# 02_MCU.net
KiCad netlist of a schematic drawn in Altium Designer
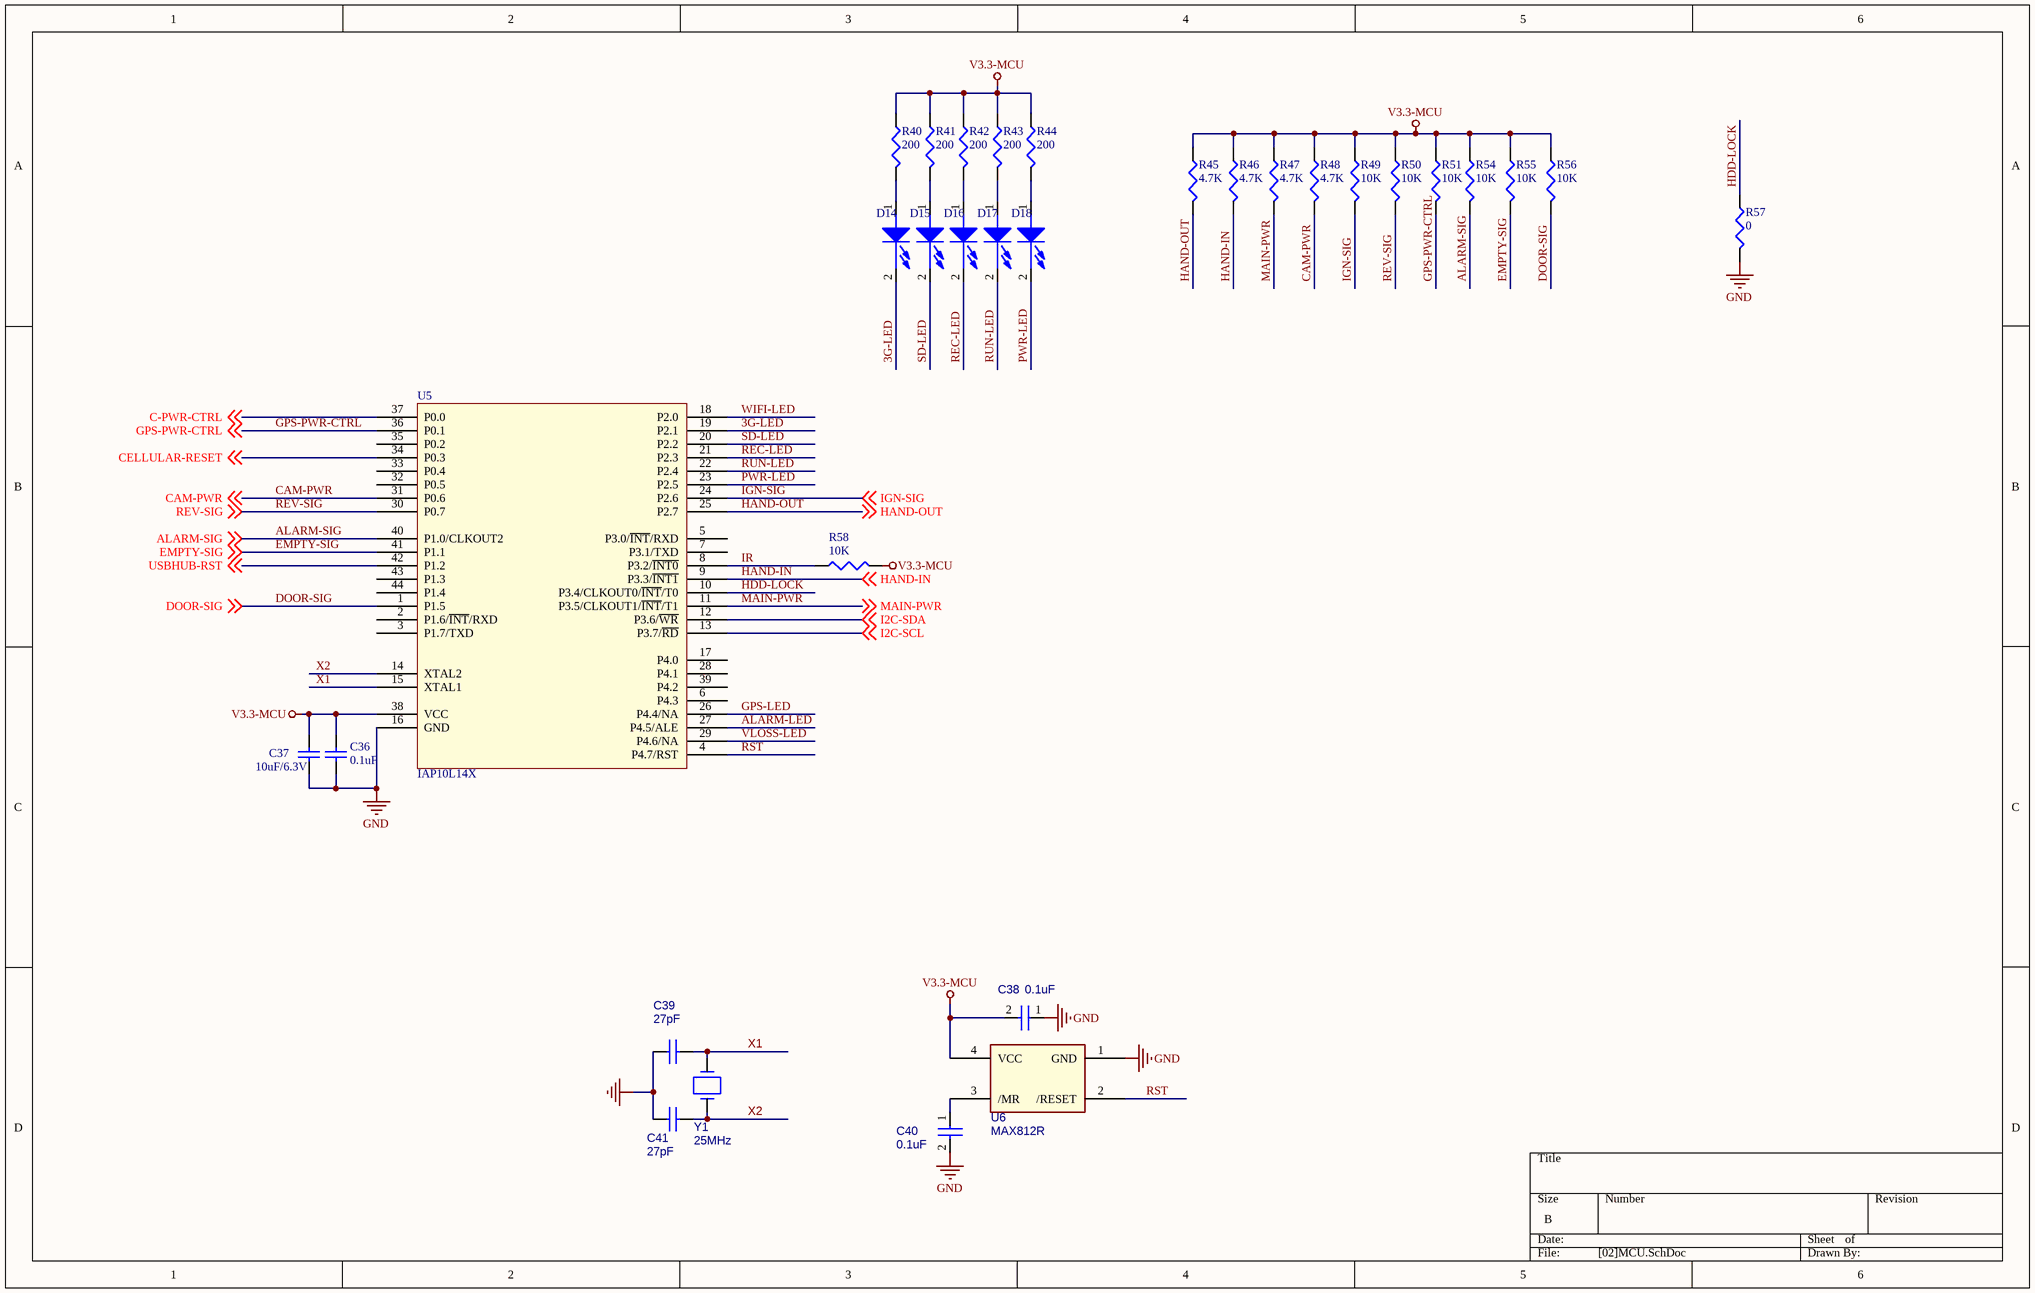
[diagram p0: [02]MCU.SchDoc]

(export (version "E")
  (design (tool "Eeschema 10.0.6"))
  (components
    (comp (ref "C36")
      (value "0.1uF")
      (footprint "0603")
      (description "Capacitor")
      (libsource (lib "Miscellaneous Devices") (part "Cap"))
    )
    (comp (ref "C37")
      (value "10uF/6.3V")
      (footprint "0805")
      (description "Capacitor")
      (libsource (lib "Miscellaneous Devices") (part "Cap"))
    )
    (comp (ref "C38") (value "0.1uF") (libsource (lib "*") (part "CAP NP_Dup2")))
    (comp (ref "C39") (value "27pF") (libsource (lib "*") (part "CAP_Dup1")))
    (comp (ref "C40") (value "0.1uF") (libsource (lib "*") (part "CAP NP_Dup2")))
    (comp (ref "C41") (value "27pF") (libsource (lib "*") (part "CAP_Dup1")))
    (comp (ref "D14") (value "LED GREEN") (footprint "LED0603") (libsource (lib "*") (part "LN01401_1")))
    (comp (ref "D15") (value "LED GREEN") (footprint "LED0603") (libsource (lib "*") (part "LN01401_1")))
    (comp (ref "D16") (value "LED GREEN") (footprint "LED0603") (libsource (lib "*") (part "LN01401_1")))
    (comp (ref "D17") (value "LED GREEN") (footprint "LED0603") (libsource (lib "*") (part "LN01401_1")))
    (comp (ref "D18") (value "LED GREEN") (footprint "LED0603") (libsource (lib "*") (part "LN01401_1")))
    (comp (ref "R40") (value "200") (footprint "0603") (libsource (lib "*") (part "CR16-1003FM")))
    (comp (ref "R41") (value "200") (footprint "0603") (libsource (lib "*") (part "CR16-1003FM")))
    (comp (ref "R42") (value "200") (footprint "0603") (libsource (lib "*") (part "CR16-1003FM")))
    (comp (ref "R43") (value "200") (footprint "0603") (libsource (lib "*") (part "CR16-1003FM")))
    (comp (ref "R44") (value "200") (footprint "0603") (libsource (lib "*") (part "CR16-1003FM")))
    (comp (ref "R45") (value "4.7K") (footprint "0603") (libsource (lib "*") (part "CR16-1003FM")))
    (comp (ref "R46") (value "4.7K") (footprint "0603") (libsource (lib "*") (part "CR16-1003FM")))
    (comp (ref "R47") (value "4.7K") (footprint "0603") (libsource (lib "*") (part "CR16-1003FM")))
    (comp (ref "R48") (value "4.7K") (footprint "0603") (libsource (lib "*") (part "CR16-1003FM")))
    (comp (ref "R49") (value "10K") (footprint "0603") (libsource (lib "*") (part "CR16-1003FM")))
    (comp (ref "R50") (value "10K") (footprint "0603") (libsource (lib "*") (part "CR16-1003FM")))
    (comp (ref "R51") (value "10K") (footprint "0603") (libsource (lib "*") (part "CR16-1003FM")))
    (comp (ref "R54") (value "10K") (footprint "0603") (libsource (lib "*") (part "CR16-1003FM")))
    (comp (ref "R55") (value "10K") (footprint "0603") (libsource (lib "*") (part "CR16-1003FM")))
    (comp (ref "R56") (value "10K") (footprint "0603") (libsource (lib "*") (part "CR16-1003FM")))
    (comp (ref "R57") (value "0") (footprint "0603") (libsource (lib "*") (part "CR16-1003FM")))
    (comp (ref "R58") (value "10K") (footprint "0603") (libsource (lib "*") (part "CR16-1003FM")))
    (comp (ref "U5") (value "IAP10L14X") (footprint "LQFP44") (libsource (lib "Schlib") (part "IAP10L14X")))
    (comp (ref "U6") (value "MAX812R") (libsource (lib "*") (part "MAX811")))
    (comp (ref "Y1") (value "25MHz") (libsource (lib "*") (part "CRYSTAL")))
  )
  (nets
    (net (code "1") (name "/3G-LED") (class "Default")
      (node (ref "D14") (pin "2") (pinfunction "CATHODE_2") (pintype "passive"))
      (node (ref "U5") (pin "19") (pinfunction "P2.1_19") (pintype "passive"))
    )
    (net (code "2") (name "/ALARM-LED") (class "Default")
      (node (ref "U5") (pin "27") (pinfunction "P4.5/ALE_27") (pintype "passive"))
    )
    (net (code "3") (name "/GPS-LED") (class "Default")
      (node (ref "U5") (pin "26") (pinfunction "P4.4/NA_26") (pintype "passive"))
    )
    (net (code "4") (name "/HDD-LOCK") (class "Default")
      (node (ref "R57") (pin "1") (pinfunction "1_1") (pintype "passive"))
      (node (ref "U5") (pin "10") (pinfunction "P3.4/CLKOUT0/~{INT}/T0_10") (pintype "passive"))
    )
    (net (code "5") (name "/IR") (class "Default")
      (node (ref "R58") (pin "1") (pinfunction "1_1") (pintype "passive"))
      (node (ref "U5") (pin "8") (pinfunction "P3.2/~{INT0}_8") (pintype "passive"))
    )
    (net (code "6") (name "/PWR-LED") (class "Default")
      (node (ref "D18") (pin "2") (pinfunction "CATHODE_2") (pintype "passive"))
      (node (ref "U5") (pin "23") (pinfunction "P2.5_23") (pintype "passive"))
    )
    (net (code "7") (name "/REC-LED") (class "Default")
      (node (ref "D16") (pin "2") (pinfunction "CATHODE_2") (pintype "passive"))
      (node (ref "U5") (pin "21") (pinfunction "P2.3_21") (pintype "passive"))
    )
    (net (code "8") (name "/RST") (class "Default")
      (node (ref "U5") (pin "4") (pinfunction "P4.7/RST_4") (pintype "passive"))
      (node (ref "U6") (pin "2") (pinfunction "/RESET_2") (pintype "passive"))
    )
    (net (code "9") (name "/RUN-LED") (class "Default")
      (node (ref "D17") (pin "2") (pinfunction "CATHODE_2") (pintype "passive"))
      (node (ref "U5") (pin "22") (pinfunction "P2.4_22") (pintype "passive"))
    )
    (net (code "10") (name "/SD-LED") (class "Default")
      (node (ref "D15") (pin "2") (pinfunction "CATHODE_2") (pintype "passive"))
      (node (ref "U5") (pin "20") (pinfunction "P2.2_20") (pintype "passive"))
    )
    (net (code "11") (name "/VLOSS-LED") (class "Default")
      (node (ref "U5") (pin "29") (pinfunction "P4.6/NA_29") (pintype "passive"))
    )
    (net (code "12") (name "/WIFI-LED") (class "Default")
      (node (ref "U5") (pin "18") (pinfunction "P2.0_18") (pintype "passive"))
    )
    (net (code "13") (name "/X1") (class "Default")
      (node (ref "C39") (pin "2") (pinfunction "2_2") (pintype "passive"))
      (node (ref "U5") (pin "15") (pinfunction "XTAL1_15") (pintype "passive"))
      (node (ref "Y1") (pin "2") (pinfunction "2_2") (pintype "passive"))
    )
    (net (code "14") (name "/X2") (class "Default")
      (node (ref "C41") (pin "2") (pinfunction "2_2") (pintype "passive"))
      (node (ref "U5") (pin "14") (pinfunction "XTAL2_14") (pintype "passive"))
      (node (ref "Y1") (pin "1") (pinfunction "1_1") (pintype "passive"))
    )
    (net (code "15") (name "ALARM-SIG") (class "Default")
      (node (ref "R54") (pin "2") (pinfunction "2_2") (pintype "passive"))
      (node (ref "U5") (pin "40") (pinfunction "P1.0/CLKOUT2_40") (pintype "passive"))
    )
    (net (code "16") (name "C-PWR-CTRL") (class "Default")
      (node (ref "U5") (pin "37") (pinfunction "P0.0_37") (pintype "passive"))
    )
    (net (code "17") (name "CAM-PWR") (class "Default")
      (node (ref "R48") (pin "2") (pinfunction "2_2") (pintype "passive"))
      (node (ref "U5") (pin "31") (pinfunction "P0.6_31") (pintype "passive"))
    )
    (net (code "18") (name "CELLULAR-RESET") (class "Default")
      (node (ref "U5") (pin "34") (pinfunction "P0.3_34") (pintype "passive"))
    )
    (net (code "19") (name "DOOR-SIG") (class "Default")
      (node (ref "R56") (pin "2") (pinfunction "2_2") (pintype "passive"))
      (node (ref "U5") (pin "1") (pinfunction "P1.5_1") (pintype "passive"))
    )
    (net (code "20") (name "EMPTY-SIG") (class "Default")
      (node (ref "R55") (pin "2") (pinfunction "2_2") (pintype "passive"))
      (node (ref "U5") (pin "41") (pinfunction "P1.1_41") (pintype "passive"))
    )
    (net (code "21") (name "GND") (class "Default")
      (node (ref "C36") (pin "1") (pinfunction "1_1") (pintype "passive"))
      (node (ref "C37") (pin "1") (pinfunction "1_1") (pintype "passive"))
      (node (ref "C38") (pin "1") (pinfunction "1_1") (pintype "passive"))
      (node (ref "C39") (pin "1") (pinfunction "1_1") (pintype "passive"))
      (node (ref "C40") (pin "2") (pinfunction "2_2") (pintype "passive"))
      (node (ref "C41") (pin "1") (pinfunction "1_1") (pintype "passive"))
      (node (ref "R57") (pin "2") (pinfunction "2_2") (pintype "passive"))
      (node (ref "U5") (pin "16") (pinfunction "GND_16") (pintype "passive"))
      (node (ref "U6") (pin "1") (pinfunction "GND_1") (pintype "passive"))
    )
    (net (code "22") (name "GPS-PWR-CTRL") (class "Default")
      (node (ref "R51") (pin "2") (pinfunction "2_2") (pintype "passive"))
      (node (ref "U5") (pin "36") (pinfunction "P0.1_36") (pintype "passive"))
    )
    (net (code "23") (name "HAND-IN") (class "Default")
      (node (ref "R46") (pin "2") (pinfunction "2_2") (pintype "passive"))
      (node (ref "U5") (pin "9") (pinfunction "P3.3/~{INT1}_9") (pintype "passive"))
    )
    (net (code "24") (name "HAND-OUT") (class "Default")
      (node (ref "R45") (pin "2") (pinfunction "2_2") (pintype "passive"))
      (node (ref "U5") (pin "25") (pinfunction "P2.7_25") (pintype "passive"))
    )
    (net (code "25") (name "I2C-SCL") (class "Default")
      (node (ref "U5") (pin "13") (pinfunction "P3.7/~{RD}_13") (pintype "passive"))
    )
    (net (code "26") (name "I2C-SDA") (class "Default")
      (node (ref "U5") (pin "12") (pinfunction "P3.6/~{WR}_12") (pintype "passive"))
    )
    (net (code "27") (name "IGN-SIG") (class "Default")
      (node (ref "R49") (pin "2") (pinfunction "2_2") (pintype "passive"))
      (node (ref "U5") (pin "24") (pinfunction "P2.6_24") (pintype "passive"))
    )
    (net (code "28") (name "MAIN-PWR") (class "Default")
      (node (ref "R47") (pin "2") (pinfunction "2_2") (pintype "passive"))
      (node (ref "U5") (pin "11") (pinfunction "P3.5/CLKOUT1/~{INT}/T1_11") (pintype "passive"))
    )
    (net (code "29") (name "Net-(D14-ANODE)") (class "Default")
      (node (ref "D14") (pin "1") (pinfunction "ANODE_1") (pintype "passive"))
      (node (ref "R40") (pin "2") (pinfunction "2_2") (pintype "passive"))
    )
    (net (code "30") (name "Net-(D15-ANODE)") (class "Default")
      (node (ref "D15") (pin "1") (pinfunction "ANODE_1") (pintype "passive"))
      (node (ref "R41") (pin "2") (pinfunction "2_2") (pintype "passive"))
    )
    (net (code "31") (name "Net-(D16-ANODE)") (class "Default")
      (node (ref "D16") (pin "1") (pinfunction "ANODE_1") (pintype "passive"))
      (node (ref "R42") (pin "2") (pinfunction "2_2") (pintype "passive"))
    )
    (net (code "32") (name "Net-(D17-ANODE)") (class "Default")
      (node (ref "D17") (pin "1") (pinfunction "ANODE_1") (pintype "passive"))
      (node (ref "R43") (pin "2") (pinfunction "2_2") (pintype "passive"))
    )
    (net (code "33") (name "Net-(D18-ANODE)") (class "Default")
      (node (ref "D18") (pin "1") (pinfunction "ANODE_1") (pintype "passive"))
      (node (ref "R44") (pin "2") (pinfunction "2_2") (pintype "passive"))
    )
    (net (code "34") (name "Net-(U6-{slash}MR)") (class "Default")
      (node (ref "C40") (pin "1") (pinfunction "1_1") (pintype "passive"))
      (node (ref "U6") (pin "3") (pinfunction "/MR_3") (pintype "passive"))
    )
    (net (code "35") (name "REV-SIG") (class "Default")
      (node (ref "R50") (pin "2") (pinfunction "2_2") (pintype "passive"))
      (node (ref "U5") (pin "30") (pinfunction "P0.7_30") (pintype "passive"))
    )
    (net (code "36") (name "USBHUB-RST") (class "Default")
      (node (ref "U5") (pin "42") (pinfunction "P1.2_42") (pintype "passive"))
    )
    (net (code "37") (name "V3.3-MCU") (class "Default")
      (node (ref "C36") (pin "2") (pinfunction "2_2") (pintype "passive"))
      (node (ref "C37") (pin "2") (pinfunction "2_2") (pintype "passive"))
      (node (ref "C38") (pin "2") (pinfunction "2_2") (pintype "passive"))
      (node (ref "R40") (pin "1") (pinfunction "1_1") (pintype "passive"))
      (node (ref "R41") (pin "1") (pinfunction "1_1") (pintype "passive"))
      (node (ref "R42") (pin "1") (pinfunction "1_1") (pintype "passive"))
      (node (ref "R43") (pin "1") (pinfunction "1_1") (pintype "passive"))
      (node (ref "R44") (pin "1") (pinfunction "1_1") (pintype "passive"))
      (node (ref "R45") (pin "1") (pinfunction "1_1") (pintype "passive"))
      (node (ref "R46") (pin "1") (pinfunction "1_1") (pintype "passive"))
      (node (ref "R47") (pin "1") (pinfunction "1_1") (pintype "passive"))
      (node (ref "R48") (pin "1") (pinfunction "1_1") (pintype "passive"))
      (node (ref "R49") (pin "1") (pinfunction "1_1") (pintype "passive"))
      (node (ref "R50") (pin "1") (pinfunction "1_1") (pintype "passive"))
      (node (ref "R51") (pin "1") (pinfunction "1_1") (pintype "passive"))
      (node (ref "R54") (pin "1") (pinfunction "1_1") (pintype "passive"))
      (node (ref "R55") (pin "1") (pinfunction "1_1") (pintype "passive"))
      (node (ref "R56") (pin "1") (pinfunction "1_1") (pintype "passive"))
      (node (ref "R58") (pin "2") (pinfunction "2_2") (pintype "passive"))
      (node (ref "U5") (pin "38") (pinfunction "VCC_38") (pintype "passive"))
      (node (ref "U6") (pin "4") (pinfunction "VCC_4") (pintype "passive"))
    )
    (net (code "38") (name "unconnected-(U5-P0.2-Pad35)") (class "Default")
      (node (ref "U5") (pin "35") (pinfunction "P0.2_35") (pintype "passive"))
    )
    (net (code "39") (name "unconnected-(U5-P0.4-Pad33)") (class "Default")
      (node (ref "U5") (pin "33") (pinfunction "P0.4_33") (pintype "passive"))
    )
    (net (code "40") (name "unconnected-(U5-P0.5-Pad32)") (class "Default")
      (node (ref "U5") (pin "32") (pinfunction "P0.5_32") (pintype "passive"))
    )
    (net (code "41") (name "unconnected-(U5-P1.3-Pad43)") (class "Default")
      (node (ref "U5") (pin "43") (pinfunction "P1.3_43") (pintype "passive"))
    )
    (net (code "42") (name "unconnected-(U5-P1.4-Pad44)") (class "Default")
      (node (ref "U5") (pin "44") (pinfunction "P1.4_44") (pintype "passive"))
    )
    (net (code "43") (name "unconnected-(U5-P1.6{slash}~{INT}{slash}RXD-Pad2)") (class "Default")
      (node (ref "U5") (pin "2") (pinfunction "P1.6/~{INT}/RXD_2") (pintype "passive"))
    )
    (net (code "44") (name "unconnected-(U5-P1.7{slash}TXD-Pad3)") (class "Default")
      (node (ref "U5") (pin "3") (pinfunction "P1.7/TXD_3") (pintype "passive"))
    )
    (net (code "45") (name "unconnected-(U5-P3.0{slash}~{INT}{slash}RXD-Pad5)") (class "Default")
      (node (ref "U5") (pin "5") (pinfunction "P3.0/~{INT}/RXD_5") (pintype "passive"))
    )
    (net (code "46") (name "unconnected-(U5-P3.1{slash}TXD-Pad7)") (class "Default")
      (node (ref "U5") (pin "7") (pinfunction "P3.1/TXD_7") (pintype "passive"))
    )
    (net (code "47") (name "unconnected-(U5-P4.0-Pad17)") (class "Default")
      (node (ref "U5") (pin "17") (pinfunction "P4.0_17") (pintype "passive"))
    )
    (net (code "48") (name "unconnected-(U5-P4.1-Pad28)") (class "Default")
      (node (ref "U5") (pin "28") (pinfunction "P4.1_28") (pintype "passive"))
    )
    (net (code "49") (name "unconnected-(U5-P4.2-Pad39)") (class "Default")
      (node (ref "U5") (pin "39") (pinfunction "P4.2_39") (pintype "passive"))
    )
    (net (code "50") (name "unconnected-(U5-P4.3-Pad6)") (class "Default")
      (node (ref "U5") (pin "6") (pinfunction "P4.3_6") (pintype "passive"))
    )
  )
)
